# SparkyJrRemorandum.net
KiCad netlist of a schematic drawn in EAGLE
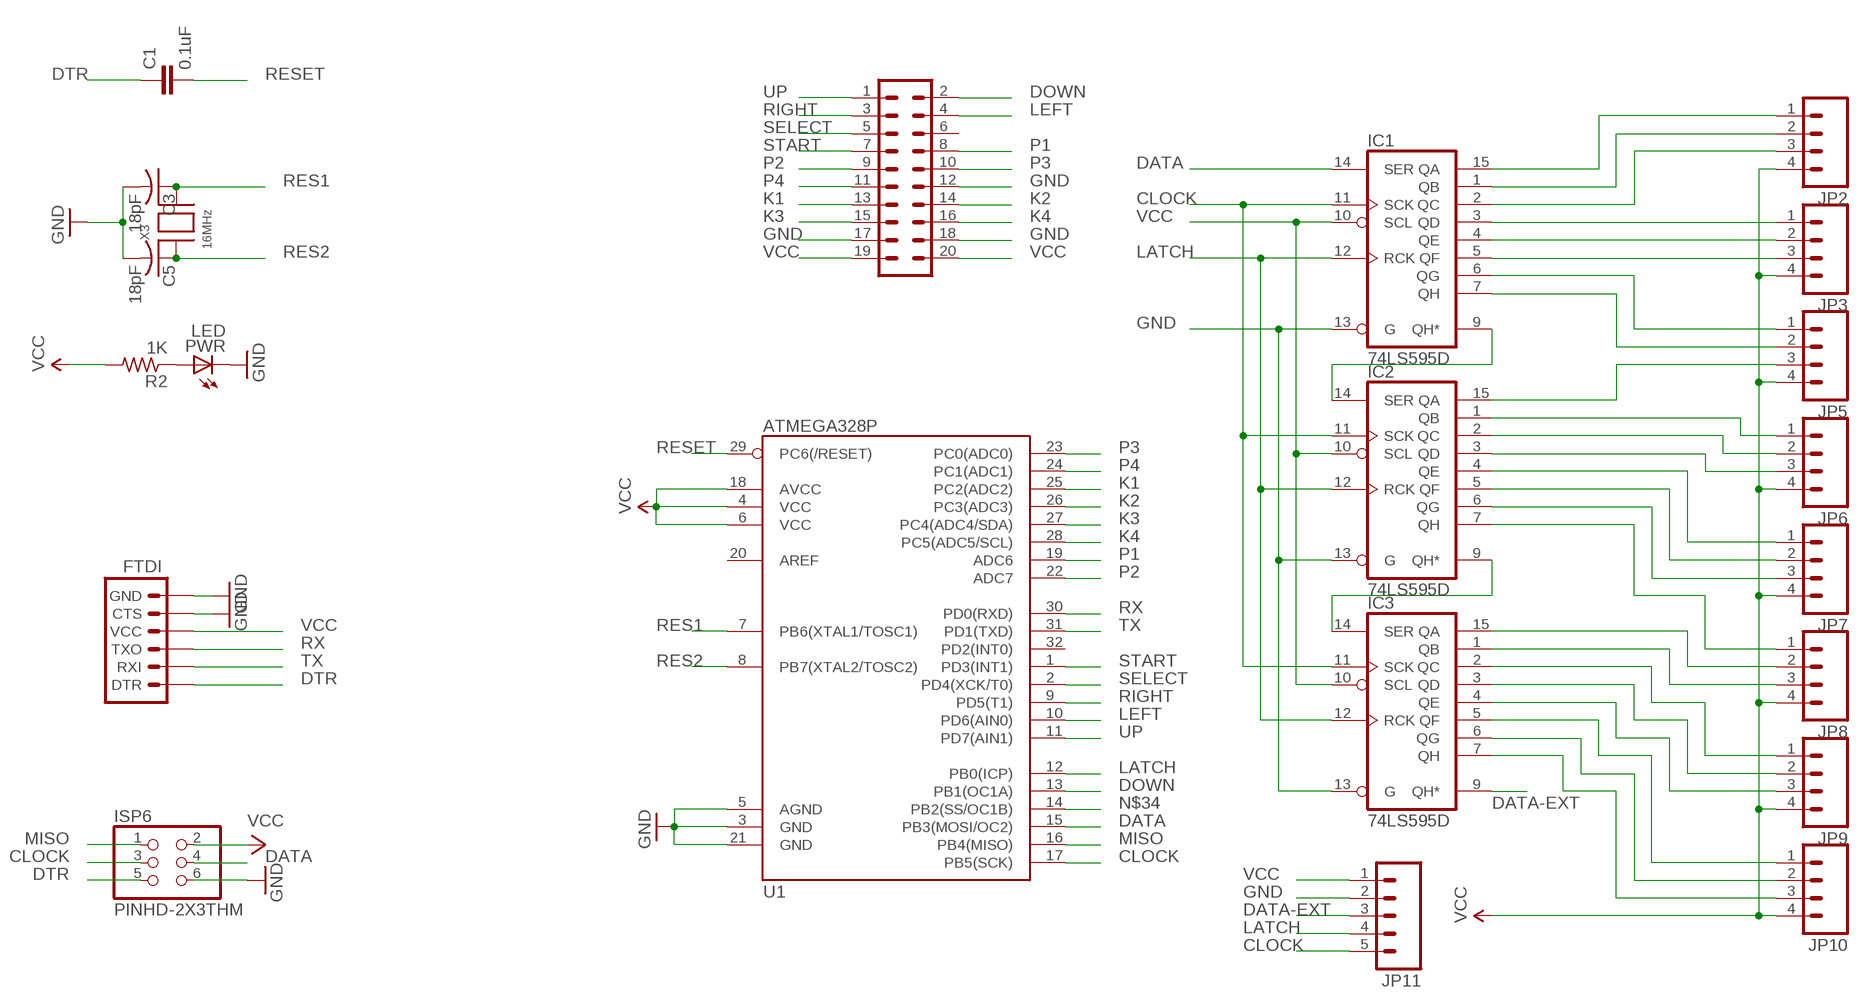
[diagram p0: schematic, sheet 1]

(export (version "E")
  (design (tool "Eeschema 10.0.6"))
  (components
    (comp (ref "C1")
      (value "0.1uF")
      (footprint "eagle-import:0805")
      (libsource (lib "eagle-import") (part "CAP0805"))
    )
    (comp (ref "C3")
      (value "18pF")
      (footprint "eagle-import:C0805K")
      (libsource (lib "eagle-import") (part "C-USC0805K"))
    )
    (comp (ref "C5")
      (value "18pF")
      (footprint "eagle-import:C0805K")
      (libsource (lib "eagle-import") (part "C-USC0805K"))
    )
    (comp (ref "FTDI")
      (value "ARDUINO_SERIAL_PROGRAMPTH")
      (footprint "eagle-import:1X06")
      (libsource (lib "eagle-import") (part "ARDUINO_SERIAL_PROGRAMPTH"))
    )
    (comp (ref "IC1")
      (value "74LS595D")
      (footprint "eagle-import:SO16")
      (libsource (lib "eagle-import") (part "74595DLS"))
    )
    (comp (ref "IC2")
      (value "74LS595D")
      (footprint "eagle-import:SO16")
      (libsource (lib "eagle-import") (part "74595DLS"))
    )
    (comp (ref "IC3")
      (value "74LS595D")
      (footprint "eagle-import:SO16")
      (libsource (lib "eagle-import") (part "74595DLS"))
    )
    (comp (ref "ISP6")
      (value "PINHD-2X3THM")
      (footprint "eagle-import:2X03")
      (libsource (lib "eagle-import") (part "PINHD-2X3"))
    )
    (comp (ref "JP2")
      (value "M04PTH")
      (footprint "eagle-import:1X04")
      (libsource (lib "eagle-import") (part "M04PTH"))
    )
    (comp (ref "JP3")
      (value "M04PTH")
      (footprint "eagle-import:1X04")
      (libsource (lib "eagle-import") (part "M04PTH"))
    )
    (comp (ref "JP5")
      (value "M04PTH")
      (footprint "eagle-import:1X04")
      (libsource (lib "eagle-import") (part "M04PTH"))
    )
    (comp (ref "JP6")
      (value "M04PTH")
      (footprint "eagle-import:1X04")
      (libsource (lib "eagle-import") (part "M04PTH"))
    )
    (comp (ref "JP7")
      (value "M04PTH")
      (footprint "eagle-import:1X04")
      (libsource (lib "eagle-import") (part "M04PTH"))
    )
    (comp (ref "JP8")
      (value "M04PTH")
      (footprint "eagle-import:1X04")
      (libsource (lib "eagle-import") (part "M04PTH"))
    )
    (comp (ref "JP9")
      (value "M04PTH")
      (footprint "eagle-import:1X04")
      (libsource (lib "eagle-import") (part "M04PTH"))
    )
    (comp (ref "JP10")
      (value "M04PTH")
      (footprint "eagle-import:1X04")
      (libsource (lib "eagle-import") (part "M04PTH"))
    )
    (comp (ref "JP11")
      (value "M05PTH")
      (footprint "eagle-import:1X05")
      (libsource (lib "eagle-import") (part "M05PTH"))
    )
    (comp (ref "PWR")
      (value "LED")
      (footprint "eagle-import:CHIPLED_0805")
      (libsource (lib "eagle-import") (part "LEDCHIPLED_0805"))
    )
    (comp (ref "R2")
      (value "1K")
      (footprint "eagle-import:R0805")
      (libsource (lib "eagle-import") (part "R-US_R0805"))
    )
    (comp (ref "U$1")
      (value "M10X2NOSILK")
      (footprint "eagle-import:2X10_NOSILK")
      (libsource (lib "eagle-import") (part "M10X2NOSILK"))
    )
    (comp (ref "U1")
      (value "ATMEGA328P")
      (footprint "eagle-import:TQFP32-08")
      (libsource (lib "eagle-import") (part "ATMEGA168"))
    )
    (comp (ref "X3")
      (value "16MHz")
      (footprint "eagle-import:NX5032")
      (libsource (lib "eagle-import") (part "XTALNX5032"))
    )
  )
  (nets
    (net (code "1") (name "/CLOCK") (class "Default")
      (node (ref "IC1") (pin "11") (pinfunction "SCK_11") (pintype "input"))
      (node (ref "IC2") (pin "11") (pinfunction "SCK_11") (pintype "input"))
      (node (ref "IC3") (pin "11") (pinfunction "SCK_11") (pintype "input"))
      (node (ref "ISP6") (pin "3") (pinfunction "3_3") (pintype "passive"))
      (node (ref "JP11") (pin "5") (pinfunction "5_5") (pintype "passive"))
      (node (ref "U1") (pin "17") (pinfunction "PB5(SCK)_17") (pintype "bidirectional"))
    )
    (net (code "2") (name "/DATA") (class "Default")
      (node (ref "IC1") (pin "14") (pinfunction "SER_14") (pintype "input"))
      (node (ref "ISP6") (pin "4") (pinfunction "4_4") (pintype "passive"))
      (node (ref "U1") (pin "15") (pinfunction "PB3(MOSI/OC2)_15") (pintype "bidirectional"))
    )
    (net (code "3") (name "/DATA-EXT") (class "Default")
      (node (ref "IC3") (pin "9") (pinfunction "QH*_9") (pintype "tri_state"))
      (node (ref "JP11") (pin "3") (pinfunction "3_3") (pintype "passive"))
    )
    (net (code "4") (name "/DOWN") (class "Default")
      (node (ref "U$1") (pin "2") (pinfunction "2_2") (pintype "passive"))
      (node (ref "U1") (pin "13") (pinfunction "PB1(OC1A)_13") (pintype "bidirectional"))
    )
    (net (code "5") (name "/DTR") (class "Default")
      (node (ref "C1") (pin "1") (pinfunction "1_1") (pintype "passive"))
      (node (ref "FTDI") (pin "1") (pinfunction "DTR_1") (pintype "passive"))
      (node (ref "ISP6") (pin "5") (pinfunction "5_5") (pintype "passive"))
    )
    (net (code "6") (name "/K1") (class "Default")
      (node (ref "U$1") (pin "13") (pinfunction "13_13") (pintype "passive"))
      (node (ref "U1") (pin "25") (pinfunction "PC2(ADC2)_25") (pintype "bidirectional"))
    )
    (net (code "7") (name "/K2") (class "Default")
      (node (ref "U$1") (pin "14") (pinfunction "14_14") (pintype "passive"))
      (node (ref "U1") (pin "26") (pinfunction "PC3(ADC3)_26") (pintype "bidirectional"))
    )
    (net (code "8") (name "/K3") (class "Default")
      (node (ref "U$1") (pin "15") (pinfunction "15_15") (pintype "passive"))
      (node (ref "U1") (pin "27") (pinfunction "PC4(ADC4/SDA)_27") (pintype "bidirectional"))
    )
    (net (code "9") (name "/K4") (class "Default")
      (node (ref "U$1") (pin "16") (pinfunction "16_16") (pintype "passive"))
      (node (ref "U1") (pin "28") (pinfunction "PC5(ADC5/SCL)_28") (pintype "bidirectional"))
    )
    (net (code "10") (name "/LATCH") (class "Default")
      (node (ref "IC1") (pin "12") (pinfunction "RCK_12") (pintype "input"))
      (node (ref "IC2") (pin "12") (pinfunction "RCK_12") (pintype "input"))
      (node (ref "IC3") (pin "12") (pinfunction "RCK_12") (pintype "input"))
      (node (ref "JP11") (pin "4") (pinfunction "4_4") (pintype "passive"))
      (node (ref "U1") (pin "12") (pinfunction "PB0(ICP)_12") (pintype "bidirectional"))
    )
    (net (code "11") (name "/LEFT") (class "Default")
      (node (ref "U$1") (pin "4") (pinfunction "4_4") (pintype "passive"))
      (node (ref "U1") (pin "10") (pinfunction "PD6(AIN0)_10") (pintype "bidirectional"))
    )
    (net (code "12") (name "/MISO") (class "Default")
      (node (ref "ISP6") (pin "1") (pinfunction "1_1") (pintype "passive"))
      (node (ref "U1") (pin "16") (pinfunction "PB4(MISO)_16") (pintype "bidirectional"))
    )
    (net (code "13") (name "/N$34") (class "Default")
      (node (ref "U1") (pin "14") (pinfunction "PB2(SS/OC1B)_14") (pintype "bidirectional"))
    )
    (net (code "14") (name "/P1") (class "Default")
      (node (ref "U$1") (pin "8") (pinfunction "8_8") (pintype "passive"))
      (node (ref "U1") (pin "19") (pinfunction "ADC6_19") (pintype "bidirectional"))
    )
    (net (code "15") (name "/P2") (class "Default")
      (node (ref "U$1") (pin "9") (pinfunction "9_9") (pintype "passive"))
      (node (ref "U1") (pin "22") (pinfunction "ADC7_22") (pintype "bidirectional"))
    )
    (net (code "16") (name "/P3") (class "Default")
      (node (ref "U$1") (pin "10") (pinfunction "10_10") (pintype "passive"))
      (node (ref "U1") (pin "23") (pinfunction "PC0(ADC0)_23") (pintype "bidirectional"))
    )
    (net (code "17") (name "/P4") (class "Default")
      (node (ref "U$1") (pin "11") (pinfunction "11_11") (pintype "passive"))
      (node (ref "U1") (pin "24") (pinfunction "PC1(ADC1)_24") (pintype "bidirectional"))
    )
    (net (code "18") (name "/RES1") (class "Default")
      (node (ref "C3") (pin "1") (pinfunction "1_1") (pintype "passive"))
      (node (ref "U1") (pin "7") (pinfunction "PB6(XTAL1/TOSC1)_7") (pintype "bidirectional"))
      (node (ref "X3") (pin "P$2") (pinfunction "P$2_P$2") (pintype "bidirectional"))
    )
    (net (code "19") (name "/RES2") (class "Default")
      (node (ref "C5") (pin "1") (pinfunction "1_1") (pintype "passive"))
      (node (ref "U1") (pin "8") (pinfunction "PB7(XTAL2/TOSC2)_8") (pintype "bidirectional"))
      (node (ref "X3") (pin "P$1") (pinfunction "P$1_P$1") (pintype "bidirectional"))
    )
    (net (code "20") (name "/RESET") (class "Default")
      (node (ref "C1") (pin "2") (pinfunction "2_2") (pintype "passive"))
      (node (ref "U1") (pin "29") (pinfunction "PC6(/RESET)_29") (pintype "bidirectional"))
    )
    (net (code "21") (name "/RIGHT") (class "Default")
      (node (ref "U$1") (pin "3") (pinfunction "3_3") (pintype "passive"))
      (node (ref "U1") (pin "9") (pinfunction "PD5(T1)_9") (pintype "bidirectional"))
    )
    (net (code "22") (name "/RX") (class "Default")
      (node (ref "FTDI") (pin "3") (pinfunction "TXO_3") (pintype "passive"))
      (node (ref "U1") (pin "30") (pinfunction "PD0(RXD)_30") (pintype "bidirectional"))
    )
    (net (code "23") (name "/SELECT") (class "Default")
      (node (ref "U$1") (pin "5") (pinfunction "5_5") (pintype "passive"))
      (node (ref "U1") (pin "2") (pinfunction "PD4(XCK/T0)_2") (pintype "bidirectional"))
    )
    (net (code "24") (name "/START") (class "Default")
      (node (ref "U$1") (pin "7") (pinfunction "7_7") (pintype "passive"))
      (node (ref "U1") (pin "1") (pinfunction "PD3(INT1)_1") (pintype "bidirectional"))
    )
    (net (code "25") (name "/TX") (class "Default")
      (node (ref "FTDI") (pin "2") (pinfunction "RXI_2") (pintype "passive"))
      (node (ref "U1") (pin "31") (pinfunction "PD1(TXD)_31") (pintype "bidirectional"))
    )
    (net (code "26") (name "/UP") (class "Default")
      (node (ref "U$1") (pin "1") (pinfunction "1_1") (pintype "passive"))
      (node (ref "U1") (pin "11") (pinfunction "PD7(AIN1)_11") (pintype "bidirectional"))
    )
    (net (code "27") (name "GND") (class "Default")
      (node (ref "C3") (pin "2") (pinfunction "2_2") (pintype "passive"))
      (node (ref "C5") (pin "2") (pinfunction "2_2") (pintype "passive"))
      (node (ref "FTDI") (pin "5") (pinfunction "CTS_5") (pintype "passive"))
      (node (ref "FTDI") (pin "6") (pinfunction "GND_6") (pintype "passive"))
      (node (ref "IC1") (pin "13") (pinfunction "G_13") (pintype "input"))
      (node (ref "IC2") (pin "13") (pinfunction "G_13") (pintype "input"))
      (node (ref "IC3") (pin "13") (pinfunction "G_13") (pintype "input"))
      (node (ref "ISP6") (pin "6") (pinfunction "6_6") (pintype "passive"))
      (node (ref "JP11") (pin "2") (pinfunction "2_2") (pintype "passive"))
      (node (ref "PWR") (pin "C") (pinfunction "C_C") (pintype "passive"))
      (node (ref "U$1") (pin "12") (pinfunction "12_12") (pintype "passive"))
      (node (ref "U$1") (pin "17") (pinfunction "17_17") (pintype "passive"))
      (node (ref "U$1") (pin "18") (pinfunction "18_18") (pintype "passive"))
      (node (ref "U1") (pin "21") (pinfunction "GND_21") (pintype "bidirectional"))
      (node (ref "U1") (pin "3") (pinfunction "GND_3") (pintype "bidirectional"))
      (node (ref "U1") (pin "5") (pinfunction "AGND_5") (pintype "bidirectional"))
    )
    (net (code "28") (name "Net-(IC1A-QA)") (class "Default")
      (node (ref "IC1") (pin "15") (pinfunction "QA_15") (pintype "tri_state"))
      (node (ref "JP2") (pin "1") (pinfunction "1_1") (pintype "passive"))
    )
    (net (code "29") (name "Net-(IC1A-QB)") (class "Default")
      (node (ref "IC1") (pin "1") (pinfunction "QB_1") (pintype "tri_state"))
      (node (ref "JP2") (pin "2") (pinfunction "2_2") (pintype "passive"))
    )
    (net (code "30") (name "Net-(IC1A-QC)") (class "Default")
      (node (ref "IC1") (pin "2") (pinfunction "QC_2") (pintype "tri_state"))
      (node (ref "JP2") (pin "3") (pinfunction "3_3") (pintype "passive"))
    )
    (net (code "31") (name "Net-(IC1A-QD)") (class "Default")
      (node (ref "IC1") (pin "3") (pinfunction "QD_3") (pintype "tri_state"))
      (node (ref "JP3") (pin "1") (pinfunction "1_1") (pintype "passive"))
    )
    (net (code "32") (name "Net-(IC1A-QE)") (class "Default")
      (node (ref "IC1") (pin "4") (pinfunction "QE_4") (pintype "tri_state"))
      (node (ref "JP3") (pin "2") (pinfunction "2_2") (pintype "passive"))
    )
    (net (code "33") (name "Net-(IC1A-QF)") (class "Default")
      (node (ref "IC1") (pin "5") (pinfunction "QF_5") (pintype "tri_state"))
      (node (ref "JP3") (pin "3") (pinfunction "3_3") (pintype "passive"))
    )
    (net (code "34") (name "Net-(IC1A-QG)") (class "Default")
      (node (ref "IC1") (pin "6") (pinfunction "QG_6") (pintype "tri_state"))
      (node (ref "JP5") (pin "1") (pinfunction "1_1") (pintype "passive"))
    )
    (net (code "35") (name "Net-(IC1A-QH)") (class "Default")
      (node (ref "IC1") (pin "7") (pinfunction "QH_7") (pintype "tri_state"))
      (node (ref "JP5") (pin "2") (pinfunction "2_2") (pintype "passive"))
    )
    (net (code "36") (name "Net-(IC1A-QH*)") (class "Default")
      (node (ref "IC1") (pin "9") (pinfunction "QH*_9") (pintype "tri_state"))
      (node (ref "IC2") (pin "14") (pinfunction "SER_14") (pintype "input"))
    )
    (net (code "37") (name "Net-(IC2A-QA)") (class "Default")
      (node (ref "IC2") (pin "15") (pinfunction "QA_15") (pintype "tri_state"))
      (node (ref "JP5") (pin "3") (pinfunction "3_3") (pintype "passive"))
    )
    (net (code "38") (name "Net-(IC2A-QB)") (class "Default")
      (node (ref "IC2") (pin "1") (pinfunction "QB_1") (pintype "tri_state"))
      (node (ref "JP6") (pin "1") (pinfunction "1_1") (pintype "passive"))
    )
    (net (code "39") (name "Net-(IC2A-QC)") (class "Default")
      (node (ref "IC2") (pin "2") (pinfunction "QC_2") (pintype "tri_state"))
      (node (ref "JP6") (pin "2") (pinfunction "2_2") (pintype "passive"))
    )
    (net (code "40") (name "Net-(IC2A-QD)") (class "Default")
      (node (ref "IC2") (pin "3") (pinfunction "QD_3") (pintype "tri_state"))
      (node (ref "JP6") (pin "3") (pinfunction "3_3") (pintype "passive"))
    )
    (net (code "41") (name "Net-(IC2A-QE)") (class "Default")
      (node (ref "IC2") (pin "4") (pinfunction "QE_4") (pintype "tri_state"))
      (node (ref "JP7") (pin "1") (pinfunction "1_1") (pintype "passive"))
    )
    (net (code "42") (name "Net-(IC2A-QF)") (class "Default")
      (node (ref "IC2") (pin "5") (pinfunction "QF_5") (pintype "tri_state"))
      (node (ref "JP7") (pin "2") (pinfunction "2_2") (pintype "passive"))
    )
    (net (code "43") (name "Net-(IC2A-QG)") (class "Default")
      (node (ref "IC2") (pin "6") (pinfunction "QG_6") (pintype "tri_state"))
      (node (ref "JP7") (pin "3") (pinfunction "3_3") (pintype "passive"))
    )
    (net (code "44") (name "Net-(IC2A-QH)") (class "Default")
      (node (ref "IC2") (pin "7") (pinfunction "QH_7") (pintype "tri_state"))
      (node (ref "JP8") (pin "1") (pinfunction "1_1") (pintype "passive"))
    )
    (net (code "45") (name "Net-(IC2A-QH*)") (class "Default")
      (node (ref "IC2") (pin "9") (pinfunction "QH*_9") (pintype "tri_state"))
      (node (ref "IC3") (pin "14") (pinfunction "SER_14") (pintype "input"))
    )
    (net (code "46") (name "Net-(IC3A-QA)") (class "Default")
      (node (ref "IC3") (pin "15") (pinfunction "QA_15") (pintype "tri_state"))
      (node (ref "JP8") (pin "2") (pinfunction "2_2") (pintype "passive"))
    )
    (net (code "47") (name "Net-(IC3A-QB)") (class "Default")
      (node (ref "IC3") (pin "1") (pinfunction "QB_1") (pintype "tri_state"))
      (node (ref "JP8") (pin "3") (pinfunction "3_3") (pintype "passive"))
    )
    (net (code "48") (name "Net-(IC3A-QC)") (class "Default")
      (node (ref "IC3") (pin "2") (pinfunction "QC_2") (pintype "tri_state"))
      (node (ref "JP9") (pin "1") (pinfunction "1_1") (pintype "passive"))
    )
    (net (code "49") (name "Net-(IC3A-QD)") (class "Default")
      (node (ref "IC3") (pin "3") (pinfunction "QD_3") (pintype "tri_state"))
      (node (ref "JP9") (pin "2") (pinfunction "2_2") (pintype "passive"))
    )
    (net (code "50") (name "Net-(IC3A-QE)") (class "Default")
      (node (ref "IC3") (pin "4") (pinfunction "QE_4") (pintype "tri_state"))
      (node (ref "JP9") (pin "3") (pinfunction "3_3") (pintype "passive"))
    )
    (net (code "51") (name "Net-(IC3A-QF)") (class "Default")
      (node (ref "IC3") (pin "5") (pinfunction "QF_5") (pintype "tri_state"))
      (node (ref "JP10") (pin "1") (pinfunction "1_1") (pintype "passive"))
    )
    (net (code "52") (name "Net-(IC3A-QG)") (class "Default")
      (node (ref "IC3") (pin "6") (pinfunction "QG_6") (pintype "tri_state"))
      (node (ref "JP10") (pin "2") (pinfunction "2_2") (pintype "passive"))
    )
    (net (code "53") (name "Net-(IC3A-QH)") (class "Default")
      (node (ref "IC3") (pin "7") (pinfunction "QH_7") (pintype "tri_state"))
      (node (ref "JP10") (pin "3") (pinfunction "3_3") (pintype "passive"))
    )
    (net (code "54") (name "Net-(PWR-PadA)") (class "Default")
      (node (ref "PWR") (pin "A") (pinfunction "A_A") (pintype "passive"))
      (node (ref "R2") (pin "1") (pinfunction "1_1") (pintype "passive"))
    )
    (net (code "55") (name "VCC") (class "Default")
      (node (ref "FTDI") (pin "4") (pinfunction "VCC_4") (pintype "passive"))
      (node (ref "IC1") (pin "10") (pinfunction "SCL_10") (pintype "input"))
      (node (ref "IC2") (pin "10") (pinfunction "SCL_10") (pintype "input"))
      (node (ref "IC3") (pin "10") (pinfunction "SCL_10") (pintype "input"))
      (node (ref "ISP6") (pin "2") (pinfunction "2_2") (pintype "passive"))
      (node (ref "JP10") (pin "4") (pinfunction "4_4") (pintype "passive"))
      (node (ref "JP11") (pin "1") (pinfunction "1_1") (pintype "passive"))
      (node (ref "JP2") (pin "4") (pinfunction "4_4") (pintype "passive"))
      (node (ref "JP3") (pin "4") (pinfunction "4_4") (pintype "passive"))
      (node (ref "JP5") (pin "4") (pinfunction "4_4") (pintype "passive"))
      (node (ref "JP6") (pin "4") (pinfunction "4_4") (pintype "passive"))
      (node (ref "JP7") (pin "4") (pinfunction "4_4") (pintype "passive"))
      (node (ref "JP8") (pin "4") (pinfunction "4_4") (pintype "passive"))
      (node (ref "JP9") (pin "4") (pinfunction "4_4") (pintype "passive"))
      (node (ref "R2") (pin "2") (pinfunction "2_2") (pintype "passive"))
      (node (ref "U$1") (pin "19") (pinfunction "19_19") (pintype "passive"))
      (node (ref "U$1") (pin "20") (pinfunction "20_20") (pintype "passive"))
      (node (ref "U1") (pin "18") (pinfunction "AVCC_18") (pintype "bidirectional"))
      (node (ref "U1") (pin "4") (pinfunction "VCC_4") (pintype "bidirectional"))
      (node (ref "U1") (pin "6") (pinfunction "VCC_6") (pintype "bidirectional"))
    )
    (net (code "56") (name "unconnected-(U$1-Pad6)") (class "Default")
      (node (ref "U$1") (pin "6") (pinfunction "6_6") (pintype "passive"))
    )
    (net (code "57") (name "unconnected-(U1-AREF-Pad20)") (class "Default")
      (node (ref "U1") (pin "20") (pinfunction "AREF_20") (pintype "bidirectional"))
    )
    (net (code "58") (name "unconnected-(U1-PD2(INT0)-Pad32)") (class "Default")
      (node (ref "U1") (pin "32") (pinfunction "PD2(INT0)_32") (pintype "bidirectional"))
    )
  )
)
